# AnalogConnectors.net
KiCad netlist of a schematic drawn in Altium Designer
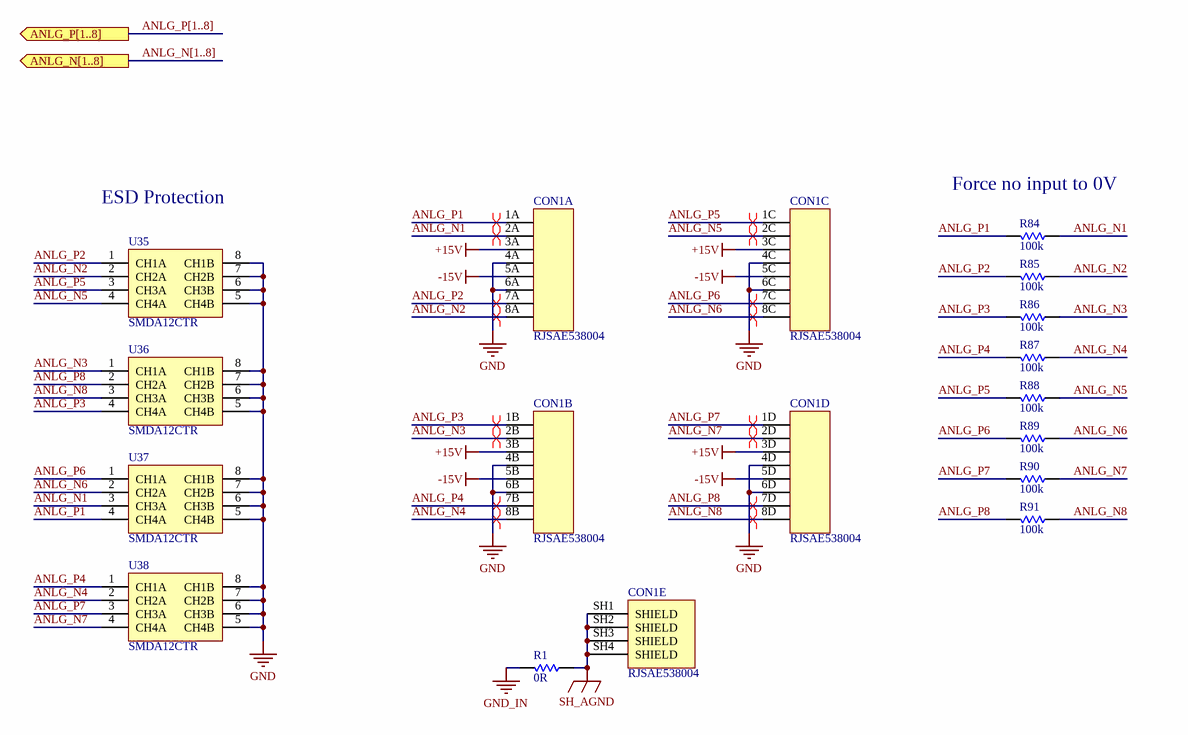
[diagram p0: AnalogConnectors.SchDoc]

(export (version "E")
  (design (tool "Eeschema 10.0.6"))
  (components
    (comp (ref "CON1")
      (value "RJSAE538004")
      (footprint "RJSAE538004")
      (description "CONN MOD JACK 8P8C R/A SHIELDED")
      (libsource (lib "AMDC") (part "RJSAE538004"))
    )
    (comp (ref "R1")
      (value "0R")
      (footprint "1206-RES")
      (description "Resistor")
      (libsource (lib "AMDC") (part "Resistor"))
    )
    (comp (ref "R84")
      (value "100k")
      (footprint "0603-RES")
      (description "Resistor")
      (libsource (lib "AMDC") (part "Resistor"))
    )
    (comp (ref "R85")
      (value "100k")
      (footprint "0603-RES")
      (description "Resistor")
      (libsource (lib "AMDC") (part "Resistor"))
    )
    (comp (ref "R86")
      (value "100k")
      (footprint "0603-RES")
      (description "Resistor")
      (libsource (lib "AMDC") (part "Resistor"))
    )
    (comp (ref "R87")
      (value "100k")
      (footprint "0603-RES")
      (description "Resistor")
      (libsource (lib "AMDC") (part "Resistor"))
    )
    (comp (ref "R88")
      (value "100k")
      (footprint "0603-RES")
      (description "Resistor")
      (libsource (lib "AMDC") (part "Resistor"))
    )
    (comp (ref "R89")
      (value "100k")
      (footprint "0603-RES")
      (description "Resistor")
      (libsource (lib "AMDC") (part "Resistor"))
    )
    (comp (ref "R90")
      (value "100k")
      (footprint "0603-RES")
      (description "Resistor")
      (libsource (lib "AMDC") (part "Resistor"))
    )
    (comp (ref "R91")
      (value "100k")
      (footprint "0603-RES")
      (description "Resistor")
      (libsource (lib "AMDC") (part "Resistor"))
    )
    (comp (ref "U35")
      (value "SMDA12CTR")
      (footprint "SOIC127P600X175-8N")
      (description "TVS DIODE 12V 19V 8SO")
      (libsource (lib "AMDC") (part "SMDA12CTR"))
    )
    (comp (ref "U36")
      (value "SMDA12CTR")
      (footprint "SOIC127P600X175-8N")
      (description "TVS DIODE 12V 19V 8SO")
      (libsource (lib "AMDC") (part "SMDA12CTR"))
    )
    (comp (ref "U37")
      (value "SMDA12CTR")
      (footprint "SOIC127P600X175-8N")
      (description "TVS DIODE 12V 19V 8SO")
      (libsource (lib "AMDC") (part "SMDA12CTR"))
    )
    (comp (ref "U38")
      (value "SMDA12CTR")
      (footprint "SOIC127P600X175-8N")
      (description "TVS DIODE 12V 19V 8SO")
      (libsource (lib "AMDC") (part "SMDA12CTR"))
    )
  )
  (nets
    (net (code "1") (name "+15V") (class "Default")
      (node (ref "CON1") (pin "3A") (pinfunction "79_3A") (pintype "passive"))
      (node (ref "CON1") (pin "3B") (pinfunction "79_3B") (pintype "passive"))
      (node (ref "CON1") (pin "3C") (pinfunction "79_3C") (pintype "passive"))
      (node (ref "CON1") (pin "3D") (pinfunction "79_3D") (pintype "passive"))
    )
    (net (code "2") (name "-15V") (class "Default")
      (node (ref "CON1") (pin "5A") (pinfunction "79_5A") (pintype "passive"))
      (node (ref "CON1") (pin "5B") (pinfunction "79_5B") (pintype "passive"))
      (node (ref "CON1") (pin "5C") (pinfunction "79_5C") (pintype "passive"))
      (node (ref "CON1") (pin "5D") (pinfunction "79_5D") (pintype "passive"))
    )
    (net (code "3") (name "/ANLG_N1") (class "Default")
      (node (ref "CON1") (pin "2A") (pinfunction "79_2A") (pintype "passive"))
      (node (ref "R84") (pin "1") (pinfunction "1_1") (pintype "passive"))
      (node (ref "U37") (pin "3") (pinfunction "CH3A_3") (pintype "passive"))
    )
    (net (code "4") (name "/ANLG_N2") (class "Default")
      (node (ref "CON1") (pin "8A") (pinfunction "79_8A") (pintype "passive"))
      (node (ref "R85") (pin "1") (pinfunction "1_1") (pintype "passive"))
      (node (ref "U35") (pin "2") (pinfunction "CH2A_2") (pintype "passive"))
    )
    (net (code "5") (name "/ANLG_N3") (class "Default")
      (node (ref "CON1") (pin "2B") (pinfunction "79_2B") (pintype "passive"))
      (node (ref "R86") (pin "1") (pinfunction "1_1") (pintype "passive"))
      (node (ref "U36") (pin "1") (pinfunction "CH1A_1") (pintype "passive"))
    )
    (net (code "6") (name "/ANLG_N4") (class "Default")
      (node (ref "CON1") (pin "8B") (pinfunction "79_8B") (pintype "passive"))
      (node (ref "R87") (pin "1") (pinfunction "1_1") (pintype "passive"))
      (node (ref "U38") (pin "2") (pinfunction "CH2A_2") (pintype "passive"))
    )
    (net (code "7") (name "/ANLG_N5") (class "Default")
      (node (ref "CON1") (pin "2C") (pinfunction "79_2C") (pintype "passive"))
      (node (ref "R88") (pin "1") (pinfunction "1_1") (pintype "passive"))
      (node (ref "U35") (pin "4") (pinfunction "CH4A_4") (pintype "passive"))
    )
    (net (code "8") (name "/ANLG_N6") (class "Default")
      (node (ref "CON1") (pin "8C") (pinfunction "79_8C") (pintype "passive"))
      (node (ref "R89") (pin "1") (pinfunction "1_1") (pintype "passive"))
      (node (ref "U37") (pin "2") (pinfunction "CH2A_2") (pintype "passive"))
    )
    (net (code "9") (name "/ANLG_N7") (class "Default")
      (node (ref "CON1") (pin "2D") (pinfunction "79_2D") (pintype "passive"))
      (node (ref "R90") (pin "1") (pinfunction "1_1") (pintype "passive"))
      (node (ref "U38") (pin "4") (pinfunction "CH4A_4") (pintype "passive"))
    )
    (net (code "10") (name "/ANLG_N8") (class "Default")
      (node (ref "CON1") (pin "8D") (pinfunction "79_8D") (pintype "passive"))
      (node (ref "R91") (pin "1") (pinfunction "1_1") (pintype "passive"))
      (node (ref "U36") (pin "3") (pinfunction "CH3A_3") (pintype "passive"))
    )
    (net (code "12") (name "/ANLG_P1") (class "Default")
      (node (ref "CON1") (pin "1A") (pinfunction "79_1A") (pintype "passive"))
      (node (ref "R84") (pin "2") (pinfunction "2_2") (pintype "passive"))
      (node (ref "U37") (pin "4") (pinfunction "CH4A_4") (pintype "passive"))
    )
    (net (code "13") (name "/ANLG_P2") (class "Default")
      (node (ref "CON1") (pin "7A") (pinfunction "79_7A") (pintype "passive"))
      (node (ref "R85") (pin "2") (pinfunction "2_2") (pintype "passive"))
      (node (ref "U35") (pin "1") (pinfunction "CH1A_1") (pintype "passive"))
    )
    (net (code "14") (name "/ANLG_P3") (class "Default")
      (node (ref "CON1") (pin "1B") (pinfunction "79_1B") (pintype "passive"))
      (node (ref "R86") (pin "2") (pinfunction "2_2") (pintype "passive"))
      (node (ref "U36") (pin "4") (pinfunction "CH4A_4") (pintype "passive"))
    )
    (net (code "15") (name "/ANLG_P4") (class "Default")
      (node (ref "CON1") (pin "7B") (pinfunction "79_7B") (pintype "passive"))
      (node (ref "R87") (pin "2") (pinfunction "2_2") (pintype "passive"))
      (node (ref "U38") (pin "1") (pinfunction "CH1A_1") (pintype "passive"))
    )
    (net (code "16") (name "/ANLG_P5") (class "Default")
      (node (ref "CON1") (pin "1C") (pinfunction "79_1C") (pintype "passive"))
      (node (ref "R88") (pin "2") (pinfunction "2_2") (pintype "passive"))
      (node (ref "U35") (pin "3") (pinfunction "CH3A_3") (pintype "passive"))
    )
    (net (code "17") (name "/ANLG_P6") (class "Default")
      (node (ref "CON1") (pin "7C") (pinfunction "79_7C") (pintype "passive"))
      (node (ref "R89") (pin "2") (pinfunction "2_2") (pintype "passive"))
      (node (ref "U37") (pin "1") (pinfunction "CH1A_1") (pintype "passive"))
    )
    (net (code "18") (name "/ANLG_P7") (class "Default")
      (node (ref "CON1") (pin "1D") (pinfunction "79_1D") (pintype "passive"))
      (node (ref "R90") (pin "2") (pinfunction "2_2") (pintype "passive"))
      (node (ref "U38") (pin "3") (pinfunction "CH3A_3") (pintype "passive"))
    )
    (net (code "19") (name "/ANLG_P8") (class "Default")
      (node (ref "CON1") (pin "7D") (pinfunction "79_7D") (pintype "passive"))
      (node (ref "R91") (pin "2") (pinfunction "2_2") (pintype "passive"))
      (node (ref "U36") (pin "2") (pinfunction "CH2A_2") (pintype "passive"))
    )
    (net (code "21") (name "GND") (class "Default")
      (node (ref "CON1") (pin "4A") (pinfunction "79_4A") (pintype "passive"))
      (node (ref "CON1") (pin "4B") (pinfunction "79_4B") (pintype "passive"))
      (node (ref "CON1") (pin "4C") (pinfunction "79_4C") (pintype "passive"))
      (node (ref "CON1") (pin "4D") (pinfunction "79_4D") (pintype "passive"))
      (node (ref "CON1") (pin "6A") (pinfunction "79_6A") (pintype "passive"))
      (node (ref "CON1") (pin "6B") (pinfunction "79_6B") (pintype "passive"))
      (node (ref "CON1") (pin "6C") (pinfunction "79_6C") (pintype "passive"))
      (node (ref "CON1") (pin "6D") (pinfunction "79_6D") (pintype "passive"))
      (node (ref "U35") (pin "5") (pinfunction "CH4B_5") (pintype "passive"))
      (node (ref "U35") (pin "6") (pinfunction "CH3B_6") (pintype "passive"))
      (node (ref "U35") (pin "7") (pinfunction "CH2B_7") (pintype "passive"))
      (node (ref "U35") (pin "8") (pinfunction "CH1B_8") (pintype "passive"))
      (node (ref "U36") (pin "5") (pinfunction "CH4B_5") (pintype "passive"))
      (node (ref "U36") (pin "6") (pinfunction "CH3B_6") (pintype "passive"))
      (node (ref "U36") (pin "7") (pinfunction "CH2B_7") (pintype "passive"))
      (node (ref "U36") (pin "8") (pinfunction "CH1B_8") (pintype "passive"))
      (node (ref "U37") (pin "5") (pinfunction "CH4B_5") (pintype "passive"))
      (node (ref "U37") (pin "6") (pinfunction "CH3B_6") (pintype "passive"))
      (node (ref "U37") (pin "7") (pinfunction "CH2B_7") (pintype "passive"))
      (node (ref "U37") (pin "8") (pinfunction "CH1B_8") (pintype "passive"))
      (node (ref "U38") (pin "5") (pinfunction "CH4B_5") (pintype "passive"))
      (node (ref "U38") (pin "6") (pinfunction "CH3B_6") (pintype "passive"))
      (node (ref "U38") (pin "7") (pinfunction "CH2B_7") (pintype "passive"))
      (node (ref "U38") (pin "8") (pinfunction "CH1B_8") (pintype "passive"))
    )
    (net (code "22") (name "GND_IN") (class "Default")
      (node (ref "R1") (pin "2") (pinfunction "2_2") (pintype "passive"))
    )
    (net (code "23") (name "SH_AGND") (class "Default")
      (node (ref "CON1") (pin "SH1") (pinfunction "SHIELD_SH1") (pintype "passive"))
      (node (ref "CON1") (pin "SH2") (pinfunction "SHIELD_SH2") (pintype "passive"))
      (node (ref "CON1") (pin "SH3") (pinfunction "SHIELD_SH3") (pintype "passive"))
      (node (ref "CON1") (pin "SH4") (pinfunction "SHIELD_SH4") (pintype "passive"))
      (node (ref "R1") (pin "1") (pinfunction "1_1") (pintype "passive"))
    )
  )
)
